# RXX-QDSB-SCH11-V1_00.net
KiCad netlist of a schematic drawn in Altium Designer
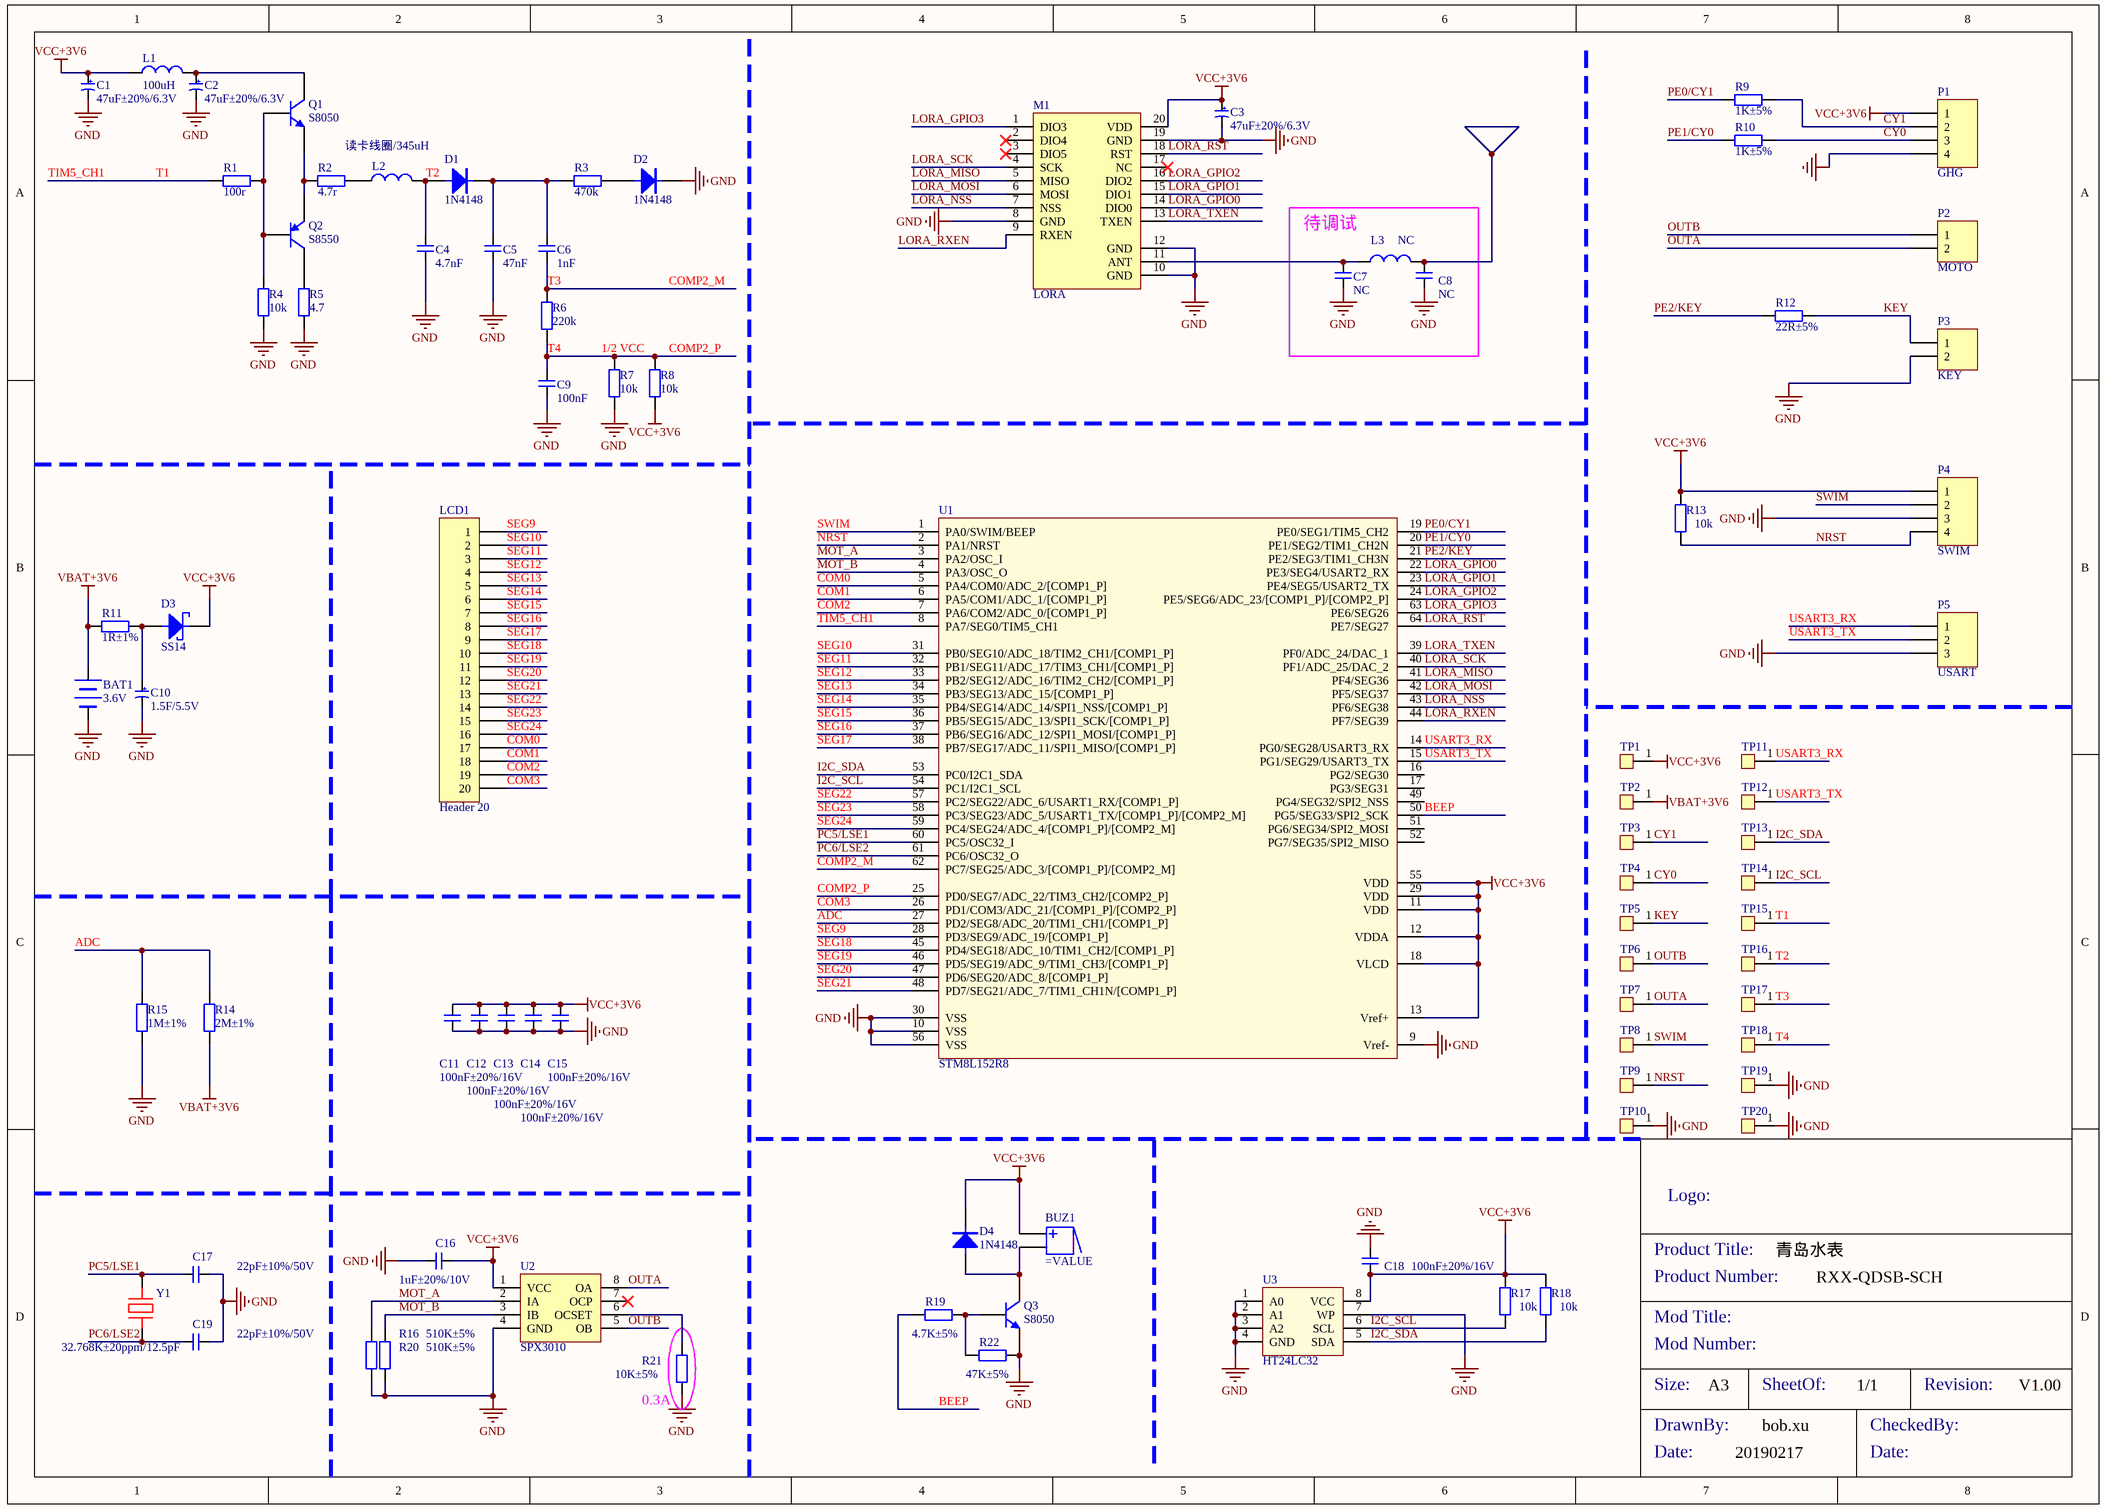
[diagram p0: RXX-QDSB-SCH11-V1.00.SchDoc]

(export (version "E")
  (design (tool "Eeschema 10.0.6"))
  (components
    (comp (ref "BAT1") (value "3.6V") (footprint "PH_2P_2R0_5R0X6R0_A") (libsource (lib "瑞臻信息") (part "BAT")))
    (comp (ref "BUZ1")
      (value "~")
      (footprint "DIP_BUZZER_2P_6R5_D12H9")
      (libsource (lib "瑞臻信息") (part "有源蜂鸣器"))
    )
    (comp (ref "C1")
      (value "47uF±20%/6.3V")
      (footprint "C3216+")
      (description "极性电容")
      (libsource (lib "瑞臻信息") (part "极性电容"))
    )
    (comp (ref "C2")
      (value "47uF±20%/6.3V")
      (footprint "C3216+")
      (description "极性电容")
      (libsource (lib "瑞臻信息") (part "极性电容"))
    )
    (comp (ref "C3")
      (value "47uF±20%/6.3V")
      (footprint "C3216+")
      (description "极性电容")
      (libsource (lib "瑞臻信息") (part "极性电容"))
    )
    (comp (ref "C4") (value "4.7nF") (description "无极性电容") (libsource (lib "瑞臻信息") (part "无极性电容")))
    (comp (ref "C5") (value "47nF") (description "无极性电容") (libsource (lib "瑞臻信息") (part "无极性电容")))
    (comp (ref "C6") (value "1nF") (description "无极性电容") (libsource (lib "瑞臻信息") (part "无极性电容")))
    (comp (ref "C7")
      (value "NC")
      (footprint "C0402")
      (description "无极性电容")
      (libsource (lib "瑞臻信息") (part "无极性电容"))
    )
    (comp (ref "C8")
      (value "NC")
      (footprint "C0402")
      (description "无极性电容")
      (libsource (lib "瑞臻信息") (part "无极性电容"))
    )
    (comp (ref "C9") (value "100nF") (description "无极性电容") (libsource (lib "瑞臻信息") (part "无极性电容")))
    (comp (ref "C10")
      (value "1.5F/5.5V")
      (footprint "CAP_2P_11R0_20X25H10_W")
      (description "极性电容")
      (libsource (lib "瑞臻信息") (part "极性电容"))
    )
    (comp (ref "C11")
      (value "100nF±20%/16V")
      (footprint "C0402")
      (description "无极性电容")
      (libsource (lib "瑞臻信息") (part "无极性电容"))
    )
    (comp (ref "C12")
      (value "100nF±20%/16V")
      (footprint "C0402")
      (description "无极性电容")
      (libsource (lib "瑞臻信息") (part "无极性电容"))
    )
    (comp (ref "C13")
      (value "100nF±20%/16V")
      (footprint "C0402")
      (description "无极性电容")
      (libsource (lib "瑞臻信息") (part "无极性电容"))
    )
    (comp (ref "C14")
      (value "100nF±20%/16V")
      (footprint "C0402")
      (description "无极性电容")
      (libsource (lib "瑞臻信息") (part "无极性电容"))
    )
    (comp (ref "C15")
      (value "100nF±20%/16V")
      (footprint "C0402")
      (description "无极性电容")
      (libsource (lib "瑞臻信息") (part "无极性电容"))
    )
    (comp (ref "C16")
      (value "1uF±20%/10V")
      (footprint "C0402")
      (description "无极性电容")
      (libsource (lib "瑞臻信息") (part "无极性电容"))
    )
    (comp (ref "C17")
      (value "22pF±10%/50V")
      (footprint "C0402")
      (description "无极性电容")
      (libsource (lib "瑞臻信息") (part "无极性电容"))
    )
    (comp (ref "C18")
      (value "100nF±20%/16V")
      (footprint "C0402")
      (description "无极性电容")
      (libsource (lib "瑞臻信息") (part "无极性电容"))
    )
    (comp (ref "C19")
      (value "22pF±10%/50V")
      (footprint "C0402")
      (description "无极性电容")
      (libsource (lib "瑞臻信息") (part "无极性电容"))
    )
    (comp (ref "D1") (value "1N4148") (description "普通二极管") (libsource (lib "瑞臻信息") (part "普通二极管")))
    (comp (ref "D2") (value "1N4148") (description "普通二极管") (libsource (lib "瑞臻信息") (part "普通二极管")))
    (comp (ref "D3")
      (value "SS14")
      (footprint "SMA_2P_2R8X4R6")
      (description "肖特基二极管")
      (libsource (lib "瑞臻信息") (part "肖特基二极管"))
    )
    (comp (ref "D4") (value "1N4148") (description "普通二极管") (libsource (lib "瑞臻信息") (part "普通二极管")))
    (comp (ref "L1") (value "100uH") (description "普通电感") (libsource (lib "瑞臻信息") (part "普通电感")))
    (comp (ref "L2") (value "读卡线圈/345uH") (description "普通电感") (libsource (lib "瑞臻信息") (part "普通电感")))
    (comp (ref "L3")
      (value "NC")
      (footprint "L0402")
      (description "普通电感")
      (libsource (lib "瑞臻信息") (part "普通电感"))
    )
    (comp (ref "LCD1")
      (value "Header 20")
      (footprint "HDR1X20")
      (description "Header, 20-Pin")
      (fields (field (name "PUBLISHER") "Altium Limited"))
      (libsource (lib "Miscellaneous Connectors") (part "Header 20"))
    )
    (comp (ref "M1") (value "LORA") (footprint "LORA_PIN_1") (libsource (lib "瑞臻信息") (part "LORA_PIN_1")))
    (comp (ref "P1")
      (value "GHG")
      (footprint "PH_4P_2R0_5R0X10R0_A")
      (description "Header, 4-Pin")
      (fields (field (name "PUBLISHER") "Altium Limited"))
      (libsource (lib "Miscellaneous Connectors") (part "Header 4"))
    )
    (comp (ref "P2")
      (value "MOTO")
      (footprint "PH_2P_2R0_5R0X6R0_A")
      (description "Header, 2-Pin")
      (fields (field (name "PUBLISHER") "Altium Limited"))
      (libsource (lib "Miscellaneous Connectors") (part "Header 2"))
    )
    (comp (ref "P3")
      (value "KEY")
      (footprint "PH_2P_2R0_5R0X6R0_A")
      (description "Header, 2-Pin")
      (fields (field (name "PUBLISHER") "Altium Limited"))
      (libsource (lib "Miscellaneous Connectors") (part "Header 2"))
    )
    (comp (ref "P4")
      (value "SWIM")
      (footprint "PH_4P_2R0_5R0X10R0_A")
      (description "Header, 4-Pin")
      (fields (field (name "PUBLISHER") "Altium Limited"))
      (libsource (lib "Miscellaneous Connectors") (part "Header 4"))
    )
    (comp (ref "P5")
      (value "USART")
      (footprint "PH_3P_2R0_5R0X8R0_A")
      (description "Header, 3-Pin")
      (fields (field (name "PUBLISHER") "Altium Limited"))
      (libsource (lib "Miscellaneous Connectors") (part "Header 3"))
    )
    (comp (ref "Q1") (value "S8050") (description "NPN三极管") (libsource (lib "瑞臻信息") (part "NPN三极管")))
    (comp (ref "Q2") (value "S8550") (description "PNP三极管") (libsource (lib "瑞臻信息") (part "PNP三极管")))
    (comp (ref "Q3")
      (value "S8050")
      (footprint "SOT23_3P_0R95_1R3X2R9")
      (description "NPN三极管")
      (libsource (lib "瑞臻信息") (part "NPN三极管"))
    )
    (comp (ref "R1") (value "100r") (description "普通电阻") (libsource (lib "瑞臻信息") (part "普通电阻")))
    (comp (ref "R2") (value "4.7r") (description "普通电阻") (libsource (lib "瑞臻信息") (part "普通电阻")))
    (comp (ref "R3") (value "470k") (description "普通电阻") (libsource (lib "瑞臻信息") (part "普通电阻")))
    (comp (ref "R4") (value "10k") (description "普通电阻") (libsource (lib "") (part "普通电阻_1")))
    (comp (ref "R5") (value "4.7") (description "普通电阻") (libsource (lib "") (part "普通电阻_1")))
    (comp (ref "R6") (value "220k") (description "普通电阻") (libsource (lib "") (part "普通电阻_2")))
    (comp (ref "R7") (value "10k") (description "普通电阻") (libsource (lib "") (part "普通电阻_2")))
    (comp (ref "R8") (value "10k") (description "普通电阻") (libsource (lib "") (part "普通电阻_2")))
    (comp (ref "R9")
      (value "1K±5%")
      (footprint "R0402")
      (description "普通电阻")
      (libsource (lib "瑞臻信息") (part "普通电阻"))
    )
    (comp (ref "R10")
      (value "1K±5%")
      (footprint "R0402")
      (description "普通电阻")
      (libsource (lib "瑞臻信息") (part "普通电阻"))
    )
    (comp (ref "R11")
      (value "1R±1%")
      (footprint "R0805")
      (description "普通电阻")
      (libsource (lib "") (part "普通电阻_3"))
    )
    (comp (ref "R12")
      (value "22R±5%")
      (footprint "R0402")
      (description "普通电阻")
      (libsource (lib "瑞臻信息") (part "普通电阻"))
    )
    (comp (ref "R13")
      (value "10k")
      (footprint "R0402")
      (description "普通电阻")
      (libsource (lib "") (part "普通电阻_1"))
    )
    (comp (ref "R14")
      (value "2M±1%")
      (footprint "R0402")
      (description "普通电阻")
      (libsource (lib "") (part "普通电阻_2"))
    )
    (comp (ref "R15")
      (value "1M±1%")
      (footprint "R0402")
      (description "普通电阻")
      (libsource (lib "") (part "普通电阻_1"))
    )
    (comp (ref "R16")
      (value "510K±5%")
      (footprint "R0402")
      (description "普通电阻")
      (libsource (lib "") (part "普通电阻_1"))
    )
    (comp (ref "R17")
      (value "10k")
      (footprint "R0402")
      (description "普通电阻")
      (libsource (lib "") (part "普通电阻_1"))
    )
    (comp (ref "R18")
      (value "10k")
      (footprint "R0402")
      (description "普通电阻")
      (libsource (lib "") (part "普通电阻_1"))
    )
    (comp (ref "R19")
      (value "4.7K±5%")
      (footprint "R0402")
      (description "普通电阻")
      (libsource (lib "瑞臻信息") (part "普通电阻"))
    )
    (comp (ref "R20")
      (value "510K±5%")
      (footprint "R0402")
      (description "普通电阻")
      (libsource (lib "") (part "普通电阻_1"))
    )
    (comp (ref "R21")
      (value "10K±5%")
      (footprint "R0402")
      (description "普通电阻")
      (libsource (lib "") (part "普通电阻_1"))
    )
    (comp (ref "R22")
      (value "47K±5%")
      (footprint "R0402")
      (description "普通电阻")
      (libsource (lib "") (part "普通电阻_3"))
    )
    (comp (ref "TP1") (value "~") (description "测试点") (libsource (lib "瑞臻信息") (part "Test_Point")))
    (comp (ref "TP2") (value "~") (description "测试点") (libsource (lib "瑞臻信息") (part "Test_Point")))
    (comp (ref "TP3") (value "~") (description "测试点") (libsource (lib "瑞臻信息") (part "Test_Point")))
    (comp (ref "TP4") (value "~") (description "测试点") (libsource (lib "瑞臻信息") (part "Test_Point")))
    (comp (ref "TP5") (value "~") (description "测试点") (libsource (lib "瑞臻信息") (part "Test_Point")))
    (comp (ref "TP6") (value "~") (description "测试点") (libsource (lib "瑞臻信息") (part "Test_Point")))
    (comp (ref "TP7") (value "~") (description "测试点") (libsource (lib "瑞臻信息") (part "Test_Point")))
    (comp (ref "TP8") (value "~") (description "测试点") (libsource (lib "瑞臻信息") (part "Test_Point")))
    (comp (ref "TP9") (value "~") (description "测试点") (libsource (lib "瑞臻信息") (part "Test_Point")))
    (comp (ref "TP10") (value "~") (description "测试点") (libsource (lib "瑞臻信息") (part "Test_Point")))
    (comp (ref "TP11") (value "~") (description "测试点") (libsource (lib "瑞臻信息") (part "Test_Point")))
    (comp (ref "TP12") (value "~") (description "测试点") (libsource (lib "瑞臻信息") (part "Test_Point")))
    (comp (ref "TP13") (value "~") (description "测试点") (libsource (lib "瑞臻信息") (part "Test_Point")))
    (comp (ref "TP14") (value "~") (description "测试点") (libsource (lib "瑞臻信息") (part "Test_Point")))
    (comp (ref "TP15") (value "~") (description "测试点") (libsource (lib "瑞臻信息") (part "Test_Point")))
    (comp (ref "TP16") (value "~") (description "测试点") (libsource (lib "瑞臻信息") (part "Test_Point")))
    (comp (ref "TP17") (value "~") (description "测试点") (libsource (lib "瑞臻信息") (part "Test_Point")))
    (comp (ref "TP18") (value "~") (description "测试点") (libsource (lib "瑞臻信息") (part "Test_Point")))
    (comp (ref "TP19") (value "~") (description "测试点") (libsource (lib "瑞臻信息") (part "Test_Point")))
    (comp (ref "TP20") (value "~") (description "测试点") (libsource (lib "瑞臻信息") (part "Test_Point")))
    (comp (ref "U1") (value "STM8L152R8") (libsource (lib "瑞臻信息") (part "STM8L152R8")))
    (comp (ref "U2")
      (value "SPX3010")
      (footprint "SOP_8P_1R27_3R9X4R9")
      (libsource (lib "瑞臻信息") (part "SPX3010"))
    )
    (comp (ref "U3")
      (value "HT24LC32")
      (footprint "SOP_8P_1R27_3R9X4R9")
      (libsource (lib "瑞臻信息") (part "24CXX"))
    )
    (comp (ref "Y1")
      (value "32.768K±20ppm/12.5pF")
      (footprint "SMD_Crystal_2P_1R5X3R2")
      (description "两脚晶体谐振器")
      (libsource (lib "瑞臻信息") (part "两脚晶体谐振器"))
    )
  )
  (nets
    (net (code "1") (name "/1{slash}2 VCC") (class "Default")
      (node (ref "C9") (pin "1") (pinfunction "1_1") (pintype "passive"))
      (node (ref "R6") (pin "2") (pinfunction "2_2") (pintype "passive"))
      (node (ref "R7") (pin "1") (pinfunction "1_1") (pintype "passive"))
      (node (ref "R8") (pin "1") (pinfunction "1_1") (pintype "passive"))
      (node (ref "TP18") (pin "1") (pinfunction "1_1") (pintype "passive"))
      (node (ref "U1") (pin "25") (pinfunction "PD0/SEG7/ADC_22/TIM3_CH2/[COMP2_P]_25") (pintype "passive"))
    )
    (net (code "2") (name "/ADC") (class "Default")
      (node (ref "R14") (pin "1") (pinfunction "1_1") (pintype "passive"))
      (node (ref "R15") (pin "2") (pinfunction "2_2") (pintype "passive"))
      (node (ref "U1") (pin "27") (pinfunction "PD2/SEG8/ADC_20/TIM1_CH1/[COMP1_P]_27") (pintype "passive"))
    )
    (net (code "3") (name "/BEEP") (class "Default")
      (node (ref "R19") (pin "2") (pinfunction "2_2") (pintype "passive"))
      (node (ref "U1") (pin "50") (pinfunction "PG5/SEG33/SPI2_SCK_50") (pintype "passive"))
    )
    (net (code "4") (name "/COM0") (class "Default")
      (node (ref "LCD1") (pin "17") (pinfunction "17_17") (pintype "passive"))
      (node (ref "U1") (pin "5") (pinfunction "PA4/COM0/ADC_2/[COMP1_P]_5") (pintype "passive"))
    )
    (net (code "5") (name "/COM1") (class "Default")
      (node (ref "LCD1") (pin "18") (pinfunction "18_18") (pintype "passive"))
      (node (ref "U1") (pin "6") (pinfunction "PA5/COM1/ADC_1/[COMP1_P]_6") (pintype "passive"))
    )
    (net (code "6") (name "/COM2") (class "Default")
      (node (ref "LCD1") (pin "19") (pinfunction "19_19") (pintype "passive"))
      (node (ref "U1") (pin "7") (pinfunction "PA6/COM2/ADC_0/[COMP1_P]_7") (pintype "passive"))
    )
    (net (code "7") (name "/COM3") (class "Default")
      (node (ref "LCD1") (pin "20") (pinfunction "20_20") (pintype "passive"))
      (node (ref "U1") (pin "26") (pinfunction "PD1/COM3/ADC_21/[COMP1_P]/[COMP2_P]_26") (pintype "passive"))
    )
    (net (code "8") (name "/COMP2_M") (class "Default")
      (node (ref "C6") (pin "2") (pinfunction "2_2") (pintype "passive"))
      (node (ref "R6") (pin "1") (pinfunction "1_1") (pintype "passive"))
      (node (ref "TP17") (pin "1") (pinfunction "1_1") (pintype "passive"))
      (node (ref "U1") (pin "62") (pinfunction "PC7/SEG25/ADC_3/[COMP1_P]/[COMP2_M]_62") (pintype "passive"))
    )
    (net (code "9") (name "/CY0") (class "Default")
      (node (ref "P1") (pin "3") (pinfunction "3_3") (pintype "passive"))
      (node (ref "R10") (pin "1") (pinfunction "1_1") (pintype "passive"))
      (node (ref "TP4") (pin "1") (pinfunction "1_1") (pintype "passive"))
    )
    (net (code "10") (name "/CY1") (class "Default")
      (node (ref "P1") (pin "2") (pinfunction "2_2") (pintype "passive"))
      (node (ref "R9") (pin "1") (pinfunction "1_1") (pintype "passive"))
      (node (ref "TP3") (pin "1") (pinfunction "1_1") (pintype "passive"))
    )
    (net (code "11") (name "/I2C_SCL") (class "Default")
      (node (ref "R17") (pin "1") (pinfunction "1_1") (pintype "passive"))
      (node (ref "TP14") (pin "1") (pinfunction "1_1") (pintype "passive"))
      (node (ref "U1") (pin "54") (pinfunction "PC1/I2C1_SCL_54") (pintype "passive"))
      (node (ref "U3") (pin "6") (pinfunction "SCL_6") (pintype "passive"))
    )
    (net (code "12") (name "/I2C_SDA") (class "Default")
      (node (ref "R18") (pin "1") (pinfunction "1_1") (pintype "passive"))
      (node (ref "TP13") (pin "1") (pinfunction "1_1") (pintype "passive"))
      (node (ref "U1") (pin "53") (pinfunction "PC0/I2C1_SDA_53") (pintype "passive"))
      (node (ref "U3") (pin "5") (pinfunction "SDA_5") (pintype "passive"))
    )
    (net (code "13") (name "/KEY") (class "Default")
      (node (ref "P3") (pin "1") (pinfunction "1_1") (pintype "passive"))
      (node (ref "R12") (pin "1") (pinfunction "1_1") (pintype "passive"))
      (node (ref "TP5") (pin "1") (pinfunction "1_1") (pintype "passive"))
    )
    (net (code "14") (name "/LORA_GPIO0") (class "Default")
      (node (ref "M1") (pin "14") (pinfunction "DIO0_14") (pintype "passive"))
      (node (ref "U1") (pin "22") (pinfunction "PE3/SEG4/USART2_RX_22") (pintype "passive"))
    )
    (net (code "15") (name "/LORA_GPIO1") (class "Default")
      (node (ref "M1") (pin "15") (pinfunction "DIO1_15") (pintype "passive"))
      (node (ref "U1") (pin "23") (pinfunction "PE4/SEG5/USART2_TX_23") (pintype "passive"))
    )
    (net (code "16") (name "/LORA_GPIO2") (class "Default")
      (node (ref "M1") (pin "16") (pinfunction "DIO2_16") (pintype "passive"))
      (node (ref "U1") (pin "24") (pinfunction "PE5/SEG6/ADC_23/[COMP1_P]/[COMP2_P]_24") (pintype "passive"))
    )
    (net (code "17") (name "/LORA_GPIO3") (class "Default")
      (node (ref "M1") (pin "1") (pinfunction "DIO3_1") (pintype "passive"))
      (node (ref "U1") (pin "63") (pinfunction "PE6/SEG26_63") (pintype "passive"))
    )
    (net (code "18") (name "/LORA_MISO") (class "Default")
      (node (ref "M1") (pin "5") (pinfunction "MISO_5") (pintype "passive"))
      (node (ref "U1") (pin "41") (pinfunction "PF4/SEG36_41") (pintype "passive"))
    )
    (net (code "19") (name "/LORA_MOSI") (class "Default")
      (node (ref "M1") (pin "6") (pinfunction "MOSI_6") (pintype "passive"))
      (node (ref "U1") (pin "42") (pinfunction "PF5/SEG37_42") (pintype "passive"))
    )
    (net (code "20") (name "/LORA_NSS") (class "Default")
      (node (ref "M1") (pin "7") (pinfunction "NSS_7") (pintype "passive"))
      (node (ref "U1") (pin "43") (pinfunction "PF6/SEG38_43") (pintype "passive"))
    )
    (net (code "21") (name "/LORA_RST") (class "Default")
      (node (ref "M1") (pin "18") (pinfunction "RST_18") (pintype "passive"))
      (node (ref "U1") (pin "64") (pinfunction "PE7/SEG27_64") (pintype "passive"))
    )
    (net (code "22") (name "/LORA_RXEN") (class "Default")
      (node (ref "M1") (pin "9") (pinfunction "RXEN_9") (pintype "passive"))
      (node (ref "U1") (pin "44") (pinfunction "PF7/SEG39_44") (pintype "passive"))
    )
    (net (code "23") (name "/LORA_SCK") (class "Default")
      (node (ref "M1") (pin "4") (pinfunction "SCK_4") (pintype "passive"))
      (node (ref "U1") (pin "40") (pinfunction "PF1/ADC_25/DAC_2_40") (pintype "passive"))
    )
    (net (code "24") (name "/LORA_TXEN") (class "Default")
      (node (ref "M1") (pin "13") (pinfunction "TXEN_13") (pintype "passive"))
      (node (ref "U1") (pin "39") (pinfunction "PF0/ADC_24/DAC_1_39") (pintype "passive"))
    )
    (net (code "25") (name "/MOT_A") (class "Default")
      (node (ref "R16") (pin "2") (pinfunction "2_2") (pintype "passive"))
      (node (ref "U1") (pin "3") (pinfunction "PA2/OSC_I_3") (pintype "passive"))
      (node (ref "U2") (pin "2") (pinfunction "IA_2") (pintype "passive"))
    )
    (net (code "26") (name "/MOT_B") (class "Default")
      (node (ref "R20") (pin "2") (pinfunction "2_2") (pintype "passive"))
      (node (ref "U1") (pin "4") (pinfunction "PA3/OSC_O_4") (pintype "passive"))
      (node (ref "U2") (pin "3") (pinfunction "IB_3") (pintype "passive"))
    )
    (net (code "27") (name "/NRST") (class "Default")
      (node (ref "P4") (pin "4") (pinfunction "4_4") (pintype "passive"))
      (node (ref "R13") (pin "1") (pinfunction "1_1") (pintype "passive"))
      (node (ref "TP9") (pin "1") (pinfunction "1_1") (pintype "passive"))
      (node (ref "U1") (pin "2") (pinfunction "PA1/NRST_2") (pintype "passive"))
    )
    (net (code "28") (name "/OUTA") (class "Default")
      (node (ref "P2") (pin "2") (pinfunction "2_2") (pintype "passive"))
      (node (ref "TP7") (pin "1") (pinfunction "1_1") (pintype "passive"))
      (node (ref "U2") (pin "8") (pinfunction "OA_8") (pintype "passive"))
    )
    (net (code "29") (name "/OUTB") (class "Default")
      (node (ref "P2") (pin "1") (pinfunction "1_1") (pintype "passive"))
      (node (ref "TP6") (pin "1") (pinfunction "1_1") (pintype "passive"))
      (node (ref "U2") (pin "5") (pinfunction "OB_5") (pintype "passive"))
    )
    (net (code "30") (name "/PC5{slash}LSE1") (class "Default")
      (node (ref "C17") (pin "2") (pinfunction "2_2") (pintype "passive"))
      (node (ref "U1") (pin "60") (pinfunction "PC5/OSC32_I_60") (pintype "passive"))
      (node (ref "Y1") (pin "2") (pinfunction "2_2") (pintype "passive"))
    )
    (net (code "31") (name "/PC6{slash}LSE2") (class "Default")
      (node (ref "C19") (pin "2") (pinfunction "2_2") (pintype "passive"))
      (node (ref "U1") (pin "61") (pinfunction "PC6/OSC32_O_61") (pintype "passive"))
      (node (ref "Y1") (pin "1") (pinfunction "1_1") (pintype "passive"))
    )
    (net (code "32") (name "/PE0{slash}CY1") (class "Default")
      (node (ref "R9") (pin "2") (pinfunction "2_2") (pintype "passive"))
      (node (ref "U1") (pin "19") (pinfunction "PE0/SEG1/TIM5_CH2_19") (pintype "passive"))
    )
    (net (code "33") (name "/PE1{slash}CY0") (class "Default")
      (node (ref "R10") (pin "2") (pinfunction "2_2") (pintype "passive"))
      (node (ref "U1") (pin "20") (pinfunction "PE1/SEG2/TIM1_CH2N_20") (pintype "passive"))
    )
    (net (code "34") (name "/PE2{slash}KEY") (class "Default")
      (node (ref "R12") (pin "2") (pinfunction "2_2") (pintype "passive"))
      (node (ref "U1") (pin "21") (pinfunction "PE2/SEG3/TIM1_CH3N_21") (pintype "passive"))
    )
    (net (code "35") (name "/SEG9") (class "Default")
      (node (ref "LCD1") (pin "1") (pinfunction "1_1") (pintype "passive"))
      (node (ref "U1") (pin "28") (pinfunction "PD3/SEG9/ADC_19/[COMP1_P]_28") (pintype "passive"))
    )
    (net (code "36") (name "/SEG10") (class "Default")
      (node (ref "LCD1") (pin "2") (pinfunction "2_2") (pintype "passive"))
      (node (ref "U1") (pin "31") (pinfunction "PB0/SEG10/ADC_18/TIM2_CH1/[COMP1_P]_31") (pintype "passive"))
    )
    (net (code "37") (name "/SEG11") (class "Default")
      (node (ref "LCD1") (pin "3") (pinfunction "3_3") (pintype "passive"))
      (node (ref "U1") (pin "32") (pinfunction "PB1/SEG11/ADC_17/TIM3_CH1/[COMP1_P]_32") (pintype "passive"))
    )
    (net (code "38") (name "/SEG12") (class "Default")
      (node (ref "LCD1") (pin "4") (pinfunction "4_4") (pintype "passive"))
      (node (ref "U1") (pin "33") (pinfunction "PB2/SEG12/ADC_16/TIM2_CH2/[COMP1_P]_33") (pintype "passive"))
    )
    (net (code "39") (name "/SEG13") (class "Default")
      (node (ref "LCD1") (pin "5") (pinfunction "5_5") (pintype "passive"))
      (node (ref "U1") (pin "34") (pinfunction "PB3/SEG13/ADC_15/[COMP1_P]_34") (pintype "passive"))
    )
    (net (code "40") (name "/SEG14") (class "Default")
      (node (ref "LCD1") (pin "6") (pinfunction "6_6") (pintype "passive"))
      (node (ref "U1") (pin "35") (pinfunction "PB4/SEG14/ADC_14/SPI1_NSS/[COMP1_P]_35") (pintype "passive"))
    )
    (net (code "41") (name "/SEG15") (class "Default")
      (node (ref "LCD1") (pin "7") (pinfunction "7_7") (pintype "passive"))
      (node (ref "U1") (pin "36") (pinfunction "PB5/SEG15/ADC_13/SPI1_SCK/[COMP1_P]_36") (pintype "passive"))
    )
    (net (code "42") (name "/SEG16") (class "Default")
      (node (ref "LCD1") (pin "8") (pinfunction "8_8") (pintype "passive"))
      (node (ref "U1") (pin "37") (pinfunction "PB6/SEG16/ADC_12/SPI1_MOSI/[COMP1_P]_37") (pintype "passive"))
    )
    (net (code "43") (name "/SEG17") (class "Default")
      (node (ref "LCD1") (pin "9") (pinfunction "9_9") (pintype "passive"))
      (node (ref "U1") (pin "38") (pinfunction "PB7/SEG17/ADC_11/SPI1_MISO/[COMP1_P]_38") (pintype "passive"))
    )
    (net (code "44") (name "/SEG18") (class "Default")
      (node (ref "LCD1") (pin "10") (pinfunction "10_10") (pintype "passive"))
      (node (ref "U1") (pin "45") (pinfunction "PD4/SEG18/ADC_10/TIM1_CH2/[COMP1_P]_45") (pintype "passive"))
    )
    (net (code "45") (name "/SEG19") (class "Default")
      (node (ref "LCD1") (pin "11") (pinfunction "11_11") (pintype "passive"))
      (node (ref "U1") (pin "46") (pinfunction "PD5/SEG19/ADC_9/TIM1_CH3/[COMP1_P]_46") (pintype "passive"))
    )
    (net (code "46") (name "/SEG20") (class "Default")
      (node (ref "LCD1") (pin "12") (pinfunction "12_12") (pintype "passive"))
      (node (ref "U1") (pin "47") (pinfunction "PD6/SEG20/ADC_8/[COMP1_P]_47") (pintype "passive"))
    )
    (net (code "47") (name "/SEG21") (class "Default")
      (node (ref "LCD1") (pin "13") (pinfunction "13_13") (pintype "passive"))
      (node (ref "U1") (pin "48") (pinfunction "PD7/SEG21/ADC_7/TIM1_CH1N/[COMP1_P]_48") (pintype "passive"))
    )
    (net (code "48") (name "/SEG22") (class "Default")
      (node (ref "LCD1") (pin "14") (pinfunction "14_14") (pintype "passive"))
      (node (ref "U1") (pin "57") (pinfunction "PC2/SEG22/ADC_6/USART1_RX/[COMP1_P]_57") (pintype "passive"))
    )
    (net (code "49") (name "/SEG23") (class "Default")
      (node (ref "LCD1") (pin "15") (pinfunction "15_15") (pintype "passive"))
      (node (ref "U1") (pin "58") (pinfunction "PC3/SEG23/ADC_5/USART1_TX/[COMP1_P]/[COMP2_M]_58") (pintype "passive"))
    )
    (net (code "50") (name "/SEG24") (class "Default")
      (node (ref "LCD1") (pin "16") (pinfunction "16_16") (pintype "passive"))
      (node (ref "U1") (pin "59") (pinfunction "PC4/SEG24/ADC_4/[COMP1_P]/[COMP2_M]_59") (pintype "passive"))
    )
    (net (code "51") (name "/SWIM") (class "Default")
      (node (ref "P4") (pin "2") (pinfunction "2_2") (pintype "passive"))
      (node (ref "TP8") (pin "1") (pinfunction "1_1") (pintype "passive"))
      (node (ref "U1") (pin "1") (pinfunction "PA0/SWIM/BEEP_1") (pintype "passive"))
    )
    (net (code "52") (name "/T1") (class "Default")
      (node (ref "R1") (pin "2") (pinfunction "2_2") (pintype "passive"))
      (node (ref "TP15") (pin "1") (pinfunction "1_1") (pintype "passive"))
      (node (ref "U1") (pin "8") (pinfunction "PA7/SEG0/TIM5_CH1_8") (pintype "passive"))
    )
    (net (code "53") (name "/T2") (class "Default")
      (node (ref "C4") (pin "1") (pinfunction "1_1") (pintype "passive"))
      (node (ref "D1") (pin "1") (pinfunction "A_1") (pintype "passive"))
      (node (ref "L2") (pin "2") (pinfunction "2_2") (pintype "passive"))
      (node (ref "TP16") (pin "1") (pinfunction "1_1") (pintype "passive"))
    )
    (net (code "54") (name "/USART3_RX") (class "Default")
      (node (ref "P5") (pin "1") (pinfunction "1_1") (pintype "passive"))
      (node (ref "TP11") (pin "1") (pinfunction "1_1") (pintype "passive"))
      (node (ref "U1") (pin "14") (pinfunction "PG0/SEG28/USART3_RX_14") (pintype "passive"))
    )
    (net (code "55") (name "/USART3_TX") (class "Default")
      (node (ref "P5") (pin "2") (pinfunction "2_2") (pintype "passive"))
      (node (ref "TP12") (pin "1") (pinfunction "1_1") (pintype "passive"))
      (node (ref "U1") (pin "15") (pinfunction "PG1/SEG29/USART3_TX_15") (pintype "passive"))
    )
    (net (code "56") (name "GND") (class "Default")
      (node (ref "BAT1") (pin "2") (pintype "passive"))
      (node (ref "C1") (pin "2") (pinfunction "2_2") (pintype "passive"))
      (node (ref "C10") (pin "2") (pinfunction "2_2") (pintype "passive"))
      (node (ref "C11") (pin "2") (pinfunction "2_2") (pintype "passive"))
      (node (ref "C12") (pin "2") (pinfunction "2_2") (pintype "passive"))
      (node (ref "C13") (pin "2") (pinfunction "2_2") (pintype "passive"))
      (node (ref "C14") (pin "2") (pinfunction "2_2") (pintype "passive"))
      (node (ref "C15") (pin "2") (pinfunction "2_2") (pintype "passive"))
      (node (ref "C16") (pin "2") (pinfunction "2_2") (pintype "passive"))
      (node (ref "C17") (pin "1") (pinfunction "1_1") (pintype "passive"))
      (node (ref "C18") (pin "1") (pinfunction "1_1") (pintype "passive"))
      (node (ref "C19") (pin "1") (pinfunction "1_1") (pintype "passive"))
      (node (ref "C2") (pin "2") (pinfunction "2_2") (pintype "passive"))
      (node (ref "C3") (pin "2") (pinfunction "2_2") (pintype "passive"))
      (node (ref "C4") (pin "2") (pinfunction "2_2") (pintype "passive"))
      (node (ref "C5") (pin "2") (pinfunction "2_2") (pintype "passive"))
      (node (ref "C7") (pin "2") (pinfunction "2_2") (pintype "passive"))
      (node (ref "C8") (pin "2") (pinfunction "2_2") (pintype "passive"))
      (node (ref "C9") (pin "2") (pinfunction "2_2") (pintype "passive"))
      (node (ref "D2") (pin "2") (pinfunction "K_2") (pintype "passive"))
      (node (ref "M1") (pin "10") (pinfunction "GND_10") (pintype "passive"))
      (node (ref "M1") (pin "12") (pinfunction "GND_12") (pintype "passive"))
      (node (ref "M1") (pin "19") (pinfunction "GND_19") (pintype "passive"))
      (node (ref "M1") (pin "8") (pinfunction "GND_8") (pintype "passive"))
      (node (ref "P1") (pin "4") (pinfunction "4_4") (pintype "passive"))
      (node (ref "P3") (pin "2") (pinfunction "2_2") (pintype "passive"))
      (node (ref "P4") (pin "3") (pinfunction "3_3") (pintype "passive"))
      (node (ref "P5") (pin "3") (pinfunction "3_3") (pintype "passive"))
      (node (ref "Q3") (pin "2") (pinfunction "E_2") (pintype "passive"))
      (node (ref "R15") (pin "1") (pinfunction "1_1") (pintype "passive"))
      (node (ref "R16") (pin "1") (pinfunction "1_1") (pintype "passive"))
      (node (ref "R20") (pin "1") (pinfunction "1_1") (pintype "passive"))
      (node (ref "R21") (pin "1") (pinfunction "1_1") (pintype "passive"))
      (node (ref "R22") (pin "2") (pinfunction "2_2") (pintype "passive"))
      (node (ref "R4") (pin "1") (pinfunction "1_1") (pintype "passive"))
      (node (ref "R5") (pin "1") (pinfunction "1_1") (pintype "passive"))
      (node (ref "R7") (pin "2") (pinfunction "2_2") (pintype "passive"))
      (node (ref "TP10") (pin "1") (pinfunction "1_1") (pintype "passive"))
      (node (ref "TP19") (pin "1") (pinfunction "1_1") (pintype "passive"))
      (node (ref "TP20") (pin "1") (pinfunction "1_1") (pintype "passive"))
      (node (ref "U1") (pin "10") (pinfunction "VSS_10") (pintype "passive"))
      (node (ref "U1") (pin "30") (pinfunction "VSS_30") (pintype "passive"))
      (node (ref "U1") (pin "56") (pinfunction "VSS_56") (pintype "passive"))
      (node (ref "U1") (pin "9") (pinfunction "Vref-_9") (pintype "passive"))
      (node (ref "U2") (pin "4") (pinfunction "GND_4") (pintype "passive"))
      (node (ref "U3") (pin "1") (pinfunction "A0_1") (pintype "passive"))
      (node (ref "U3") (pin "2") (pinfunction "A1_2") (pintype "passive"))
      (node (ref "U3") (pin "3") (pinfunction "A2_3") (pintype "passive"))
      (node (ref "U3") (pin "4") (pinfunction "GND_4") (pintype "passive"))
      (node (ref "U3") (pin "7") (pinfunction "WP_7") (pintype "passive"))
    )
    (net (code "57") (name "Net-(C8-Pad1)") (class "Default")
      (node (ref "C8") (pin "1") (pinfunction "1_1") (pintype "passive"))
      (node (ref "L3") (pin "2") (pinfunction "2_2") (pintype "passive"))
    )
    (net (code "58") (name "Net-(D1-K)") (class "Default")
      (node (ref "C5") (pin "1") (pinfunction "1_1") (pintype "passive"))
      (node (ref "C6") (pin "1") (pinfunction "1_1") (pintype "passive"))
      (node (ref "D1") (pin "2") (pinfunction "K_2") (pintype "passive"))
      (node (ref "R3") (pin "2") (pinfunction "2_2") (pintype "passive"))
    )
    (net (code "59") (name "Net-(D2-A)") (class "Default")
      (node (ref "D2") (pin "1") (pinfunction "A_1") (pintype "passive"))
      (node (ref "R3") (pin "1") (pinfunction "1_1") (pintype "passive"))
    )
    (net (code "60") (name "Net-(D3-A)") (class "Default")
      (node (ref "C10") (pin "1") (pinfunction "1_1") (pintype "passive"))
      (node (ref "D3") (pin "1") (pinfunction "A_1") (pintype "passive"))
      (node (ref "R11") (pin "2") (pinfunction "2_2") (pintype "passive"))
    )
    (net (code "61") (name "Net-(D4-A)") (class "Default")
      (node (ref "BUZ1") (pin "2") (pinfunction "2_2") (pintype "passive"))
      (node (ref "D4") (pin "1") (pinfunction "A_1") (pintype "passive"))
      (node (ref "Q3") (pin "3") (pinfunction "C_3") (pintype "passive"))
    )
    (net (code "62") (name "Net-(L2-Pad1)") (class "Default")
      (node (ref "L2") (pin "1") (pinfunction "1_1") (pintype "passive"))
      (node (ref "R2") (pin "1") (pinfunction "1_1") (pintype "passive"))
    )
    (net (code "63") (name "Net-(M1-ANT)") (class "Default")
      (node (ref "C7") (pin "1") (pinfunction "1_1") (pintype "passive"))
      (node (ref "L3") (pin "1") (pinfunction "1_1") (pintype "passive"))
      (node (ref "M1") (pin "11") (pinfunction "ANT_11") (pintype "passive"))
    )
    (net (code "64") (name "Net-(Q1-B)") (class "Default")
      (node (ref "Q1") (pin "1") (pinfunction "B_1") (pintype "passive"))
      (node (ref "Q2") (pin "1") (pinfunction "B_1") (pintype "passive"))
      (node (ref "R1") (pin "1") (pinfunction "1_1") (pintype "passive"))
      (node (ref "R4") (pin "2") (pinfunction "2_2") (pintype "passive"))
    )
    (net (code "65") (name "Net-(Q1-C)") (class "Default")
      (node (ref "C2") (pin "1") (pinfunction "1_1") (pintype "passive"))
      (node (ref "L1") (pin "2") (pinfunction "2_2") (pintype "passive"))
      (node (ref "Q1") (pin "3") (pinfunction "C_3") (pintype "passive"))
    )
    (net (code "66") (name "Net-(Q1-E)") (class "Default")
      (node (ref "Q1") (pin "2") (pinfunction "E_2") (pintype "passive"))
      (node (ref "Q2") (pin "2") (pinfunction "E_2") (pintype "passive"))
      (node (ref "R2") (pin "2") (pinfunction "2_2") (pintype "passive"))
    )
    (net (code "67") (name "Net-(Q2-C)") (class "Default")
      (node (ref "Q2") (pin "3") (pinfunction "C_3") (pintype "passive"))
      (node (ref "R5") (pin "2") (pinfunction "2_2") (pintype "passive"))
    )
    (net (code "68") (name "Net-(Q3-B)") (class "Default")
      (node (ref "Q3") (pin "1") (pinfunction "B_1") (pintype "passive"))
      (node (ref "R19") (pin "1") (pinfunction "1_1") (pintype "passive"))
      (node (ref "R22") (pin "1") (pinfunction "1_1") (pintype "passive"))
    )
    (net (code "69") (name "Net-(U2-OCSET)") (class "Default")
      (node (ref "R21") (pin "2") (pinfunction "2_2") (pintype "passive"))
      (node (ref "U2") (pin "6") (pinfunction "OCSET_6") (pintype "passive"))
    )
    (net (code "70") (name "VBAT+3V6") (class "Default")
      (node (ref "BAT1") (pin "1") (pintype "passive"))
      (node (ref "R11") (pin "1") (pinfunction "1_1") (pintype "passive"))
      (node (ref "R14") (pin "2") (pinfunction "2_2") (pintype "passive"))
      (node (ref "TP2") (pin "1") (pinfunction "1_1") (pintype "passive"))
    )
    (net (code "71") (name "VCC+3V6") (class "Default")
      (node (ref "BUZ1") (pin "1") (pinfunction "1_1") (pintype "passive"))
      (node (ref "C1") (pin "1") (pinfunction "1_1") (pintype "passive"))
      (node (ref "C11") (pin "1") (pinfunction "1_1") (pintype "passive"))
      (node (ref "C12") (pin "1") (pinfunction "1_1") (pintype "passive"))
      (node (ref "C13") (pin "1") (pinfunction "1_1") (pintype "passive"))
      (node (ref "C14") (pin "1") (pinfunction "1_1") (pintype "passive"))
      (node (ref "C15") (pin "1") (pinfunction "1_1") (pintype "passive"))
      (node (ref "C16") (pin "1") (pinfunction "1_1") (pintype "passive"))
      (node (ref "C18") (pin "2") (pinfunction "2_2") (pintype "passive"))
      (node (ref "C3") (pin "1") (pinfunction "1_1") (pintype "passive"))
      (node (ref "D3") (pin "2") (pinfunction "K_2") (pintype "passive"))
      (node (ref "D4") (pin "2") (pinfunction "K_2") (pintype "passive"))
      (node (ref "L1") (pin "1") (pinfunction "1_1") (pintype "passive"))
      (node (ref "M1") (pin "20") (pinfunction "VDD_20") (pintype "passive"))
      (node (ref "P1") (pin "1") (pinfunction "1_1") (pintype "passive"))
      (node (ref "P4") (pin "1") (pinfunction "1_1") (pintype "passive"))
      (node (ref "R13") (pin "2") (pinfunction "2_2") (pintype "passive"))
      (node (ref "R17") (pin "2") (pinfunction "2_2") (pintype "passive"))
      (node (ref "R18") (pin "2") (pinfunction "2_2") (pintype "passive"))
      (node (ref "R8") (pin "2") (pinfunction "2_2") (pintype "passive"))
      (node (ref "TP1") (pin "1") (pinfunction "1_1") (pintype "passive"))
      (node (ref "U1") (pin "11") (pinfunction "VDD_11") (pintype "passive"))
      (node (ref "U1") (pin "12") (pinfunction "VDDA_12") (pintype "passive"))
      (node (ref "U1") (pin "13") (pinfunction "Vref+_13") (pintype "passive"))
      (node (ref "U1") (pin "18") (pinfunction "VLCD_18") (pintype "passive"))
      (node (ref "U1") (pin "29") (pinfunction "VDD_29") (pintype "passive"))
      (node (ref "U1") (pin "55") (pinfunction "VDD_55") (pintype "passive"))
      (node (ref "U2") (pin "1") (pinfunction "VCC_1") (pintype "passive"))
      (node (ref "U3") (pin "8") (pinfunction "VCC_8") (pintype "passive"))
    )
    (net (code "72") (name "unconnected-(M1-DIO4-Pad2)") (class "Default")
      (node (ref "M1") (pin "2") (pinfunction "DIO4_2") (pintype "passive+no_connect"))
    )
    (net (code "73") (name "unconnected-(M1-DIO5-Pad3)") (class "Default")
      (node (ref "M1") (pin "3") (pinfunction "DIO5_3") (pintype "passive+no_connect"))
    )
    (net (code "74") (name "unconnected-(M1-NC-Pad17)") (class "Default")
      (node (ref "M1") (pin "17") (pinfunction "NC_17") (pintype "passive+no_connect"))
    )
    (net (code "75") (name "unconnected-(U1-PG2{slash}SEG30-Pad16)") (class "Default")
      (node (ref "U1") (pin "16") (pinfunction "PG2/SEG30_16") (pintype "passive"))
    )
    (net (code "76") (name "unconnected-(U1-PG3{slash}SEG31-Pad17)") (class "Default")
      (node (ref "U1") (pin "17") (pinfunction "PG3/SEG31_17") (pintype "passive"))
    )
    (net (code "77") (name "unconnected-(U1-PG4{slash}SEG32{slash}SPI2_NSS-Pad49)") (class "Default")
      (node (ref "U1") (pin "49") (pinfunction "PG4/SEG32/SPI2_NSS_49") (pintype "passive"))
    )
    (net (code "78") (name "unconnected-(U1-PG6{slash}SEG34{slash}SPI2_MOSI-Pad51)") (class "Default")
      (node (ref "U1") (pin "51") (pinfunction "PG6/SEG34/SPI2_MOSI_51") (pintype "passive"))
    )
    (net (code "79") (name "unconnected-(U1-PG7{slash}SEG35{slash}SPI2_MISO-Pad52)") (class "Default")
      (node (ref "U1") (pin "52") (pinfunction "PG7/SEG35/SPI2_MISO_52") (pintype "passive"))
    )
    (net (code "80") (name "unconnected-(U2-OCP-Pad7)") (class "Default")
      (node (ref "U2") (pin "7") (pinfunction "OCP_7") (pintype "passive+no_connect"))
    )
  )
)
